# reg-board.net
KiCad netlist of a schematic drawn in EAGLE
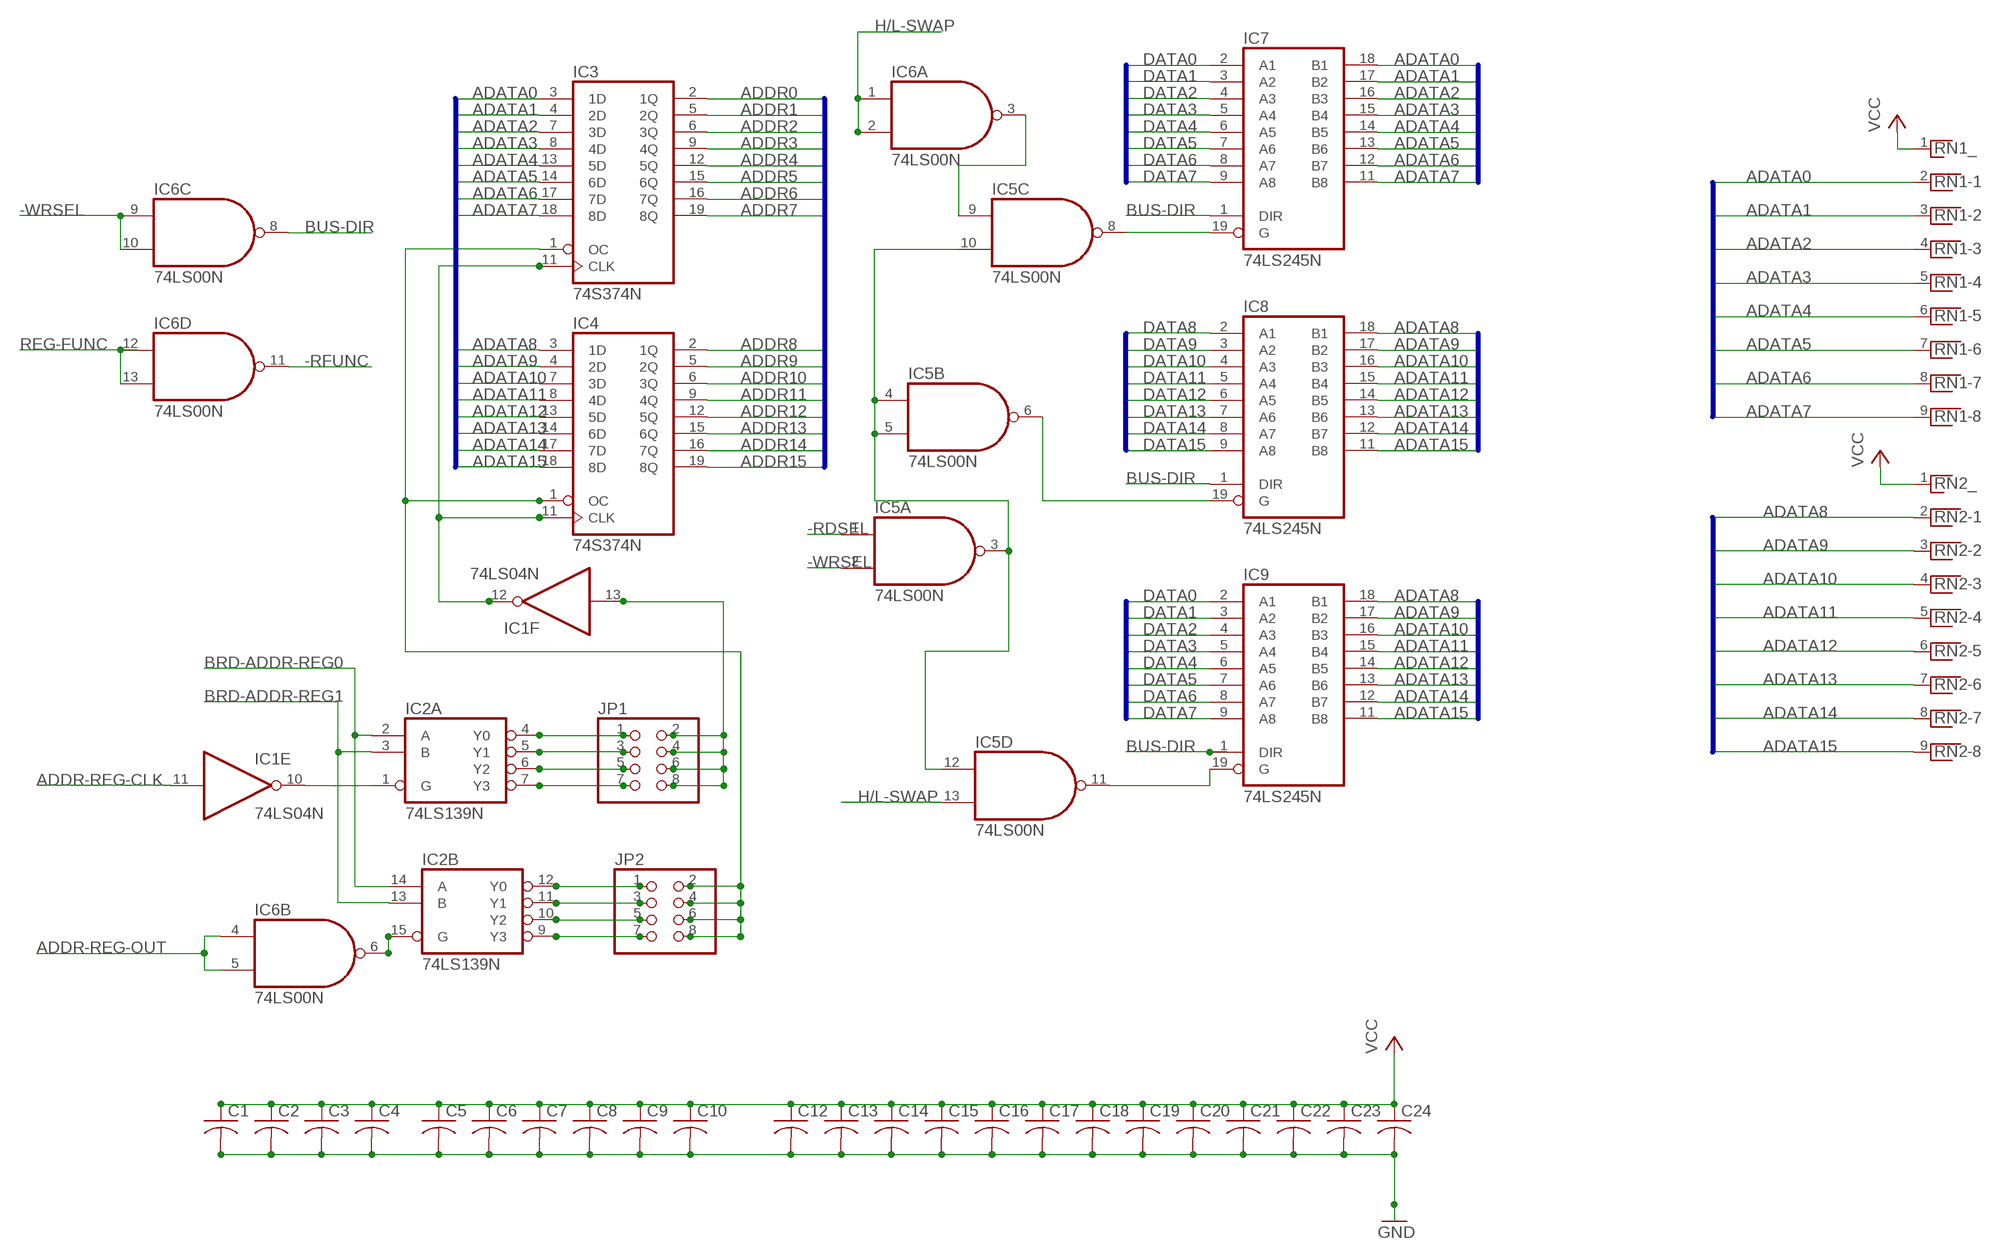
[diagram p0: schematic, sheet 1]
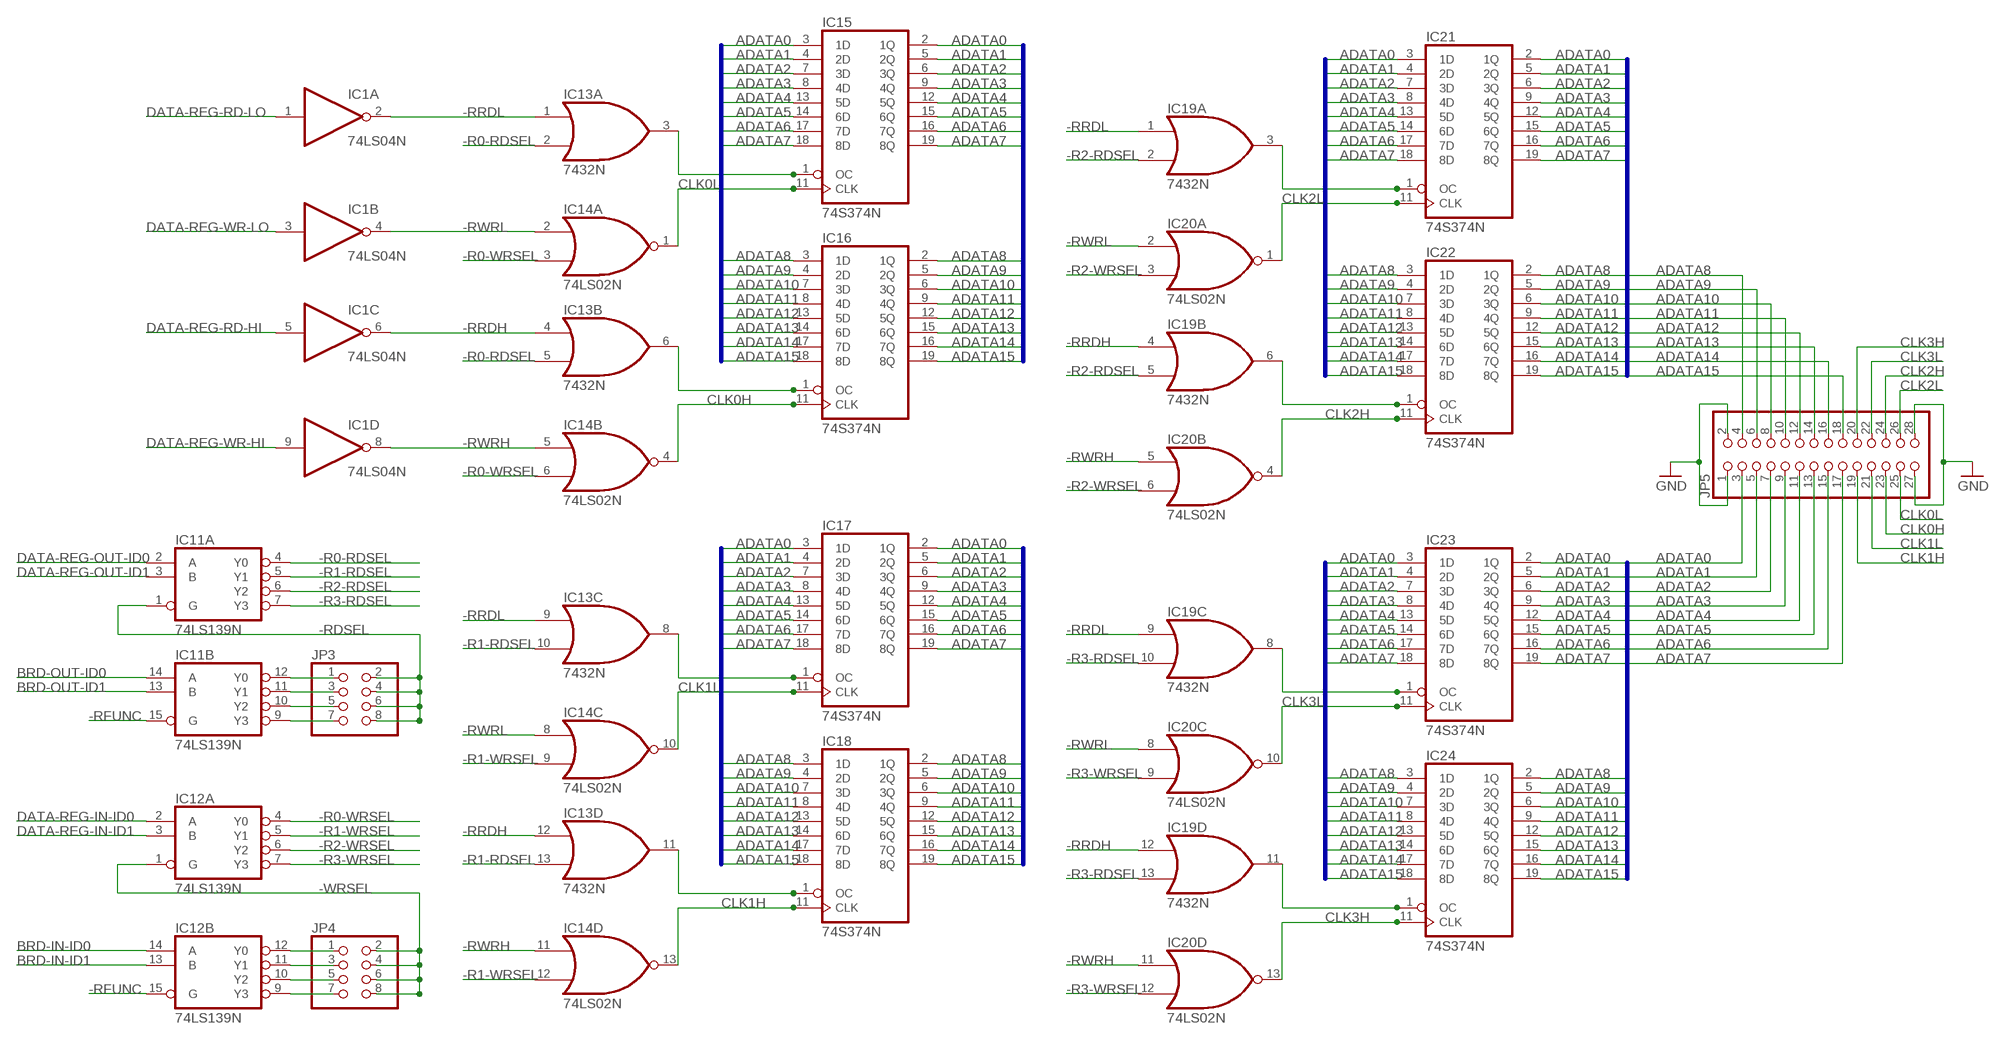
[diagram p1: schematic, sheet 2]
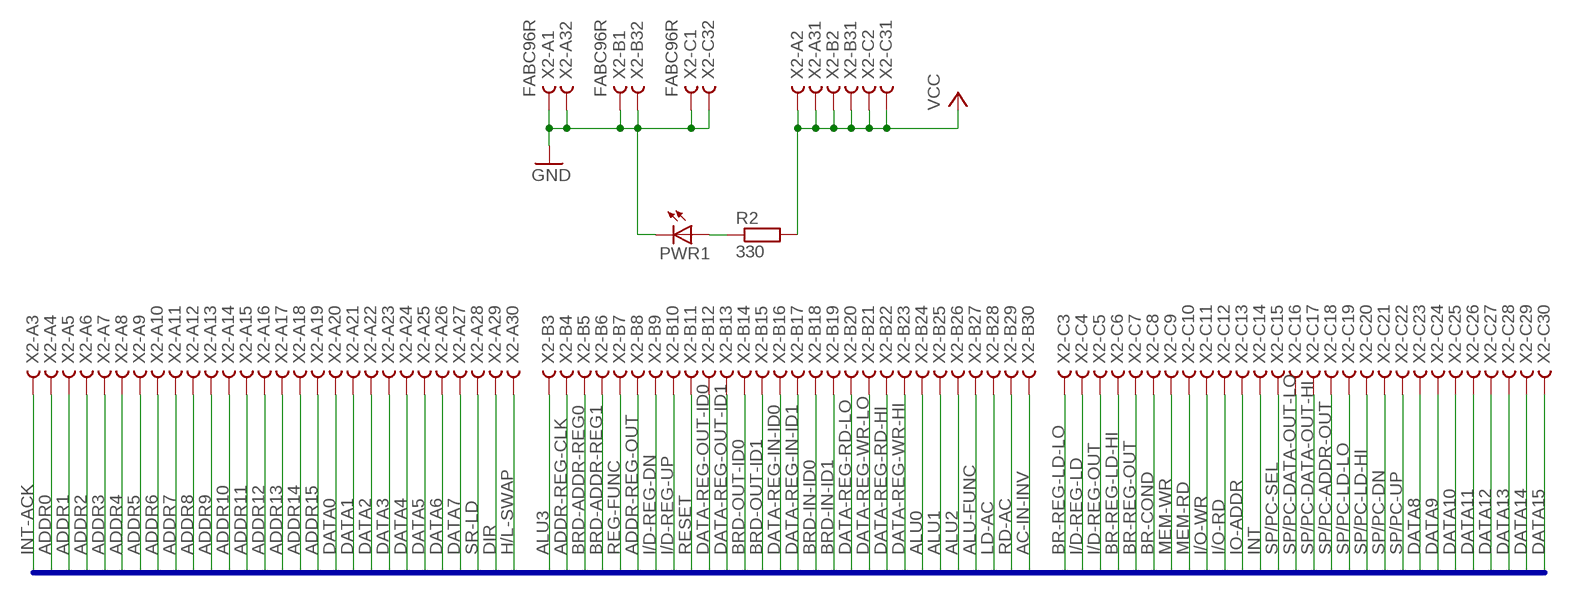
[diagram p2: schematic, sheet 3]

(export (version "E")
  (design (tool "Eeschema 10.0.6"))
  (components
    (comp (ref "IC1")
      (value "74LS04N")
      (footprint "eagle-import:DIL14")
      (libsource (lib "eagle-import") (part "7404NLS"))
    )
    (comp (ref "IC11")
      (value "74LS139N")
      (footprint "eagle-import:DIL16")
      (libsource (lib "eagle-import") (part "74139NLS"))
    )
    (comp (ref "IC12")
      (value "74LS139N")
      (footprint "eagle-import:DIL16")
      (libsource (lib "eagle-import") (part "74139NLS"))
    )
    (comp (ref "IC13")
      (value "7432N")
      (footprint "eagle-import:DIL14")
      (libsource (lib "eagle-import") (part "7432N"))
    )
    (comp (ref "IC14")
      (value "74LS02N")
      (footprint "eagle-import:DIL14")
      (libsource (lib "eagle-import") (part "7402NLS"))
    )
    (comp (ref "IC15")
      (value "74S374N")
      (footprint "eagle-import:DIL20")
      (libsource (lib "eagle-import") (part "74374NS"))
    )
    (comp (ref "IC16")
      (value "74S374N")
      (footprint "eagle-import:DIL20")
      (libsource (lib "eagle-import") (part "74374NS"))
    )
    (comp (ref "IC17")
      (value "74S374N")
      (footprint "eagle-import:DIL20")
      (libsource (lib "eagle-import") (part "74374NS"))
    )
    (comp (ref "IC18")
      (value "74S374N")
      (footprint "eagle-import:DIL20")
      (libsource (lib "eagle-import") (part "74374NS"))
    )
    (comp (ref "IC19")
      (value "7432N")
      (footprint "eagle-import:DIL14")
      (libsource (lib "eagle-import") (part "7432N"))
    )
    (comp (ref "IC20")
      (value "74LS02N")
      (footprint "eagle-import:DIL14")
      (libsource (lib "eagle-import") (part "7402NLS"))
    )
    (comp (ref "IC21")
      (value "74S374N")
      (footprint "eagle-import:DIL20")
      (libsource (lib "eagle-import") (part "74374NS"))
    )
    (comp (ref "IC22")
      (value "74S374N")
      (footprint "eagle-import:DIL20")
      (libsource (lib "eagle-import") (part "74374NS"))
    )
    (comp (ref "IC23")
      (value "74S374N")
      (footprint "eagle-import:DIL20")
      (libsource (lib "eagle-import") (part "74374NS"))
    )
    (comp (ref "IC24")
      (value "74S374N")
      (footprint "eagle-import:DIL20")
      (libsource (lib "eagle-import") (part "74374NS"))
    )
    (comp (ref "JP3")
      (value "PINHD-2X4")
      (footprint "eagle-import:2X04")
      (libsource (lib "eagle-import") (part "PINHD-2X4"))
    )
    (comp (ref "JP4")
      (value "PINHD-2X4")
      (footprint "eagle-import:2X04")
      (libsource (lib "eagle-import") (part "PINHD-2X4"))
    )
    (comp (ref "JP5")
      (value "PINHD-2X14")
      (footprint "eagle-import:2X14")
      (libsource (lib "eagle-import") (part "PINHD-2X14"))
    )
    (comp (ref "PWR1")
      (value "LED5MM")
      (footprint "eagle-import:LED5MM")
      (libsource (lib "eagle-import") (part "LED5MM"))
    )
    (comp (ref "R2")
      (value "330")
      (footprint "eagle-import:0207_10")
      (libsource (lib "eagle-import") (part "R0207/10"))
    )
    (comp (ref "X2")
      (value "FABC96R")
      (footprint "eagle-import:FABC96R")
      (libsource (lib "eagle-import") (part "FABC96R"))
    )
    (comp (ref "C1")
      (value "C-US025-040X050")
      (footprint "eagle-import:C025-040X050")
      (libsource (lib "eagle-import") (part "C-US025-040X050"))
    )
    (comp (ref "C2")
      (value "C-US025-040X050")
      (footprint "eagle-import:C025-040X050")
      (libsource (lib "eagle-import") (part "C-US025-040X050"))
    )
    (comp (ref "C3")
      (value "C-US025-040X050")
      (footprint "eagle-import:C025-040X050")
      (libsource (lib "eagle-import") (part "C-US025-040X050"))
    )
    (comp (ref "C4")
      (value "C-US025-040X050")
      (footprint "eagle-import:C025-040X050")
      (libsource (lib "eagle-import") (part "C-US025-040X050"))
    )
    (comp (ref "C5")
      (value "C-US025-040X050")
      (footprint "eagle-import:C025-040X050")
      (libsource (lib "eagle-import") (part "C-US025-040X050"))
    )
    (comp (ref "C6")
      (value "C-US025-040X050")
      (footprint "eagle-import:C025-040X050")
      (libsource (lib "eagle-import") (part "C-US025-040X050"))
    )
    (comp (ref "C7")
      (value "C-US025-040X050")
      (footprint "eagle-import:C025-040X050")
      (libsource (lib "eagle-import") (part "C-US025-040X050"))
    )
    (comp (ref "C8")
      (value "C-US025-040X050")
      (footprint "eagle-import:C025-040X050")
      (libsource (lib "eagle-import") (part "C-US025-040X050"))
    )
    (comp (ref "C9")
      (value "C-US025-040X050")
      (footprint "eagle-import:C025-040X050")
      (libsource (lib "eagle-import") (part "C-US025-040X050"))
    )
    (comp (ref "C10")
      (value "C-US025-040X050")
      (footprint "eagle-import:C025-040X050")
      (libsource (lib "eagle-import") (part "C-US025-040X050"))
    )
    (comp (ref "C12")
      (value "C-US025-040X050")
      (footprint "eagle-import:C025-040X050")
      (libsource (lib "eagle-import") (part "C-US025-040X050"))
    )
    (comp (ref "C13")
      (value "C-US025-040X050")
      (footprint "eagle-import:C025-040X050")
      (libsource (lib "eagle-import") (part "C-US025-040X050"))
    )
    (comp (ref "C14")
      (value "C-US025-040X050")
      (footprint "eagle-import:C025-040X050")
      (libsource (lib "eagle-import") (part "C-US025-040X050"))
    )
    (comp (ref "C15")
      (value "C-US025-040X050")
      (footprint "eagle-import:C025-040X050")
      (libsource (lib "eagle-import") (part "C-US025-040X050"))
    )
    (comp (ref "C16")
      (value "C-US025-040X050")
      (footprint "eagle-import:C025-040X050")
      (libsource (lib "eagle-import") (part "C-US025-040X050"))
    )
    (comp (ref "C17")
      (value "C-US025-040X050")
      (footprint "eagle-import:C025-040X050")
      (libsource (lib "eagle-import") (part "C-US025-040X050"))
    )
    (comp (ref "C18")
      (value "C-US025-040X050")
      (footprint "eagle-import:C025-040X050")
      (libsource (lib "eagle-import") (part "C-US025-040X050"))
    )
    (comp (ref "C19")
      (value "C-US025-040X050")
      (footprint "eagle-import:C025-040X050")
      (libsource (lib "eagle-import") (part "C-US025-040X050"))
    )
    (comp (ref "C20")
      (value "C-US025-040X050")
      (footprint "eagle-import:C025-040X050")
      (libsource (lib "eagle-import") (part "C-US025-040X050"))
    )
    (comp (ref "C21")
      (value "C-US025-040X050")
      (footprint "eagle-import:C025-040X050")
      (libsource (lib "eagle-import") (part "C-US025-040X050"))
    )
    (comp (ref "C22")
      (value "C-US025-040X050")
      (footprint "eagle-import:C025-040X050")
      (libsource (lib "eagle-import") (part "C-US025-040X050"))
    )
    (comp (ref "C23")
      (value "C-US025-040X050")
      (footprint "eagle-import:C025-040X050")
      (libsource (lib "eagle-import") (part "C-US025-040X050"))
    )
    (comp (ref "C24")
      (value "C-US025-040X050")
      (footprint "eagle-import:C025-040X050")
      (libsource (lib "eagle-import") (part "C-US025-040X050"))
    )
    (comp (ref "IC2")
      (value "74LS139N")
      (footprint "eagle-import:DIL16")
      (libsource (lib "eagle-import") (part "74139NLS"))
    )
    (comp (ref "IC3")
      (value "74S374N")
      (footprint "eagle-import:DIL20")
      (libsource (lib "eagle-import") (part "74374NS"))
    )
    (comp (ref "IC4")
      (value "74S374N")
      (footprint "eagle-import:DIL20")
      (libsource (lib "eagle-import") (part "74374NS"))
    )
    (comp (ref "IC5")
      (value "74LS00N")
      (footprint "eagle-import:DIL14")
      (libsource (lib "eagle-import") (part "7400NLS"))
    )
    (comp (ref "IC6")
      (value "74LS00N")
      (footprint "eagle-import:DIL14")
      (libsource (lib "eagle-import") (part "7400NLS"))
    )
    (comp (ref "IC7")
      (value "74LS245N")
      (footprint "eagle-import:DIL20")
      (libsource (lib "eagle-import") (part "74245NLS"))
    )
    (comp (ref "IC8")
      (value "74LS245N")
      (footprint "eagle-import:DIL20")
      (libsource (lib "eagle-import") (part "74245NLS"))
    )
    (comp (ref "IC9")
      (value "74LS245N")
      (footprint "eagle-import:DIL20")
      (libsource (lib "eagle-import") (part "74245NLS"))
    )
    (comp (ref "JP1")
      (value "PINHD-2X4")
      (footprint "eagle-import:2X04")
      (libsource (lib "eagle-import") (part "PINHD-2X4"))
    )
    (comp (ref "JP2")
      (value "PINHD-2X4")
      (footprint "eagle-import:2X04")
      (libsource (lib "eagle-import") (part "PINHD-2X4"))
    )
    (comp (ref "RN1")
      (value "RNX8")
      (footprint "eagle-import:RN-9")
      (libsource (lib "eagle-import") (part "RNX8"))
    )
    (comp (ref "RN2")
      (value "RNX8")
      (footprint "eagle-import:RN-9")
      (libsource (lib "eagle-import") (part "RNX8"))
    )
  )
  (nets
    (net (code "1") (name "-R0-RDSEL") (class "Default")
      (node (ref "IC11") (pin "4") (pinfunction "Y0_4") (pintype "output"))
      (node (ref "IC13") (pin "2") (pinfunction "I1_2") (pintype "input"))
      (node (ref "IC13") (pin "5") (pinfunction "I1_5") (pintype "input"))
    )
    (net (code "2") (name "-R0-WRSEL") (class "Default")
      (node (ref "IC12") (pin "4") (pinfunction "Y0_4") (pintype "output"))
      (node (ref "IC14") (pin "3") (pinfunction "I1_3") (pintype "input"))
      (node (ref "IC14") (pin "6") (pinfunction "I1_6") (pintype "input"))
    )
    (net (code "3") (name "-R1-RDSEL") (class "Default")
      (node (ref "IC11") (pin "5") (pinfunction "Y1_5") (pintype "output"))
      (node (ref "IC13") (pin "10") (pinfunction "I1_10") (pintype "input"))
      (node (ref "IC13") (pin "13") (pinfunction "I1_13") (pintype "input"))
    )
    (net (code "4") (name "-R1-WRSEL") (class "Default")
      (node (ref "IC12") (pin "5") (pinfunction "Y1_5") (pintype "output"))
      (node (ref "IC14") (pin "12") (pinfunction "I1_12") (pintype "input"))
      (node (ref "IC14") (pin "9") (pinfunction "I1_9") (pintype "input"))
    )
    (net (code "5") (name "-R2-RDSEL") (class "Default")
      (node (ref "IC11") (pin "6") (pinfunction "Y2_6") (pintype "output"))
      (node (ref "IC19") (pin "2") (pinfunction "I1_2") (pintype "input"))
      (node (ref "IC19") (pin "5") (pinfunction "I1_5") (pintype "input"))
    )
    (net (code "6") (name "-R2-WRSEL") (class "Default")
      (node (ref "IC12") (pin "6") (pinfunction "Y2_6") (pintype "output"))
      (node (ref "IC20") (pin "3") (pinfunction "I1_3") (pintype "input"))
      (node (ref "IC20") (pin "6") (pinfunction "I1_6") (pintype "input"))
    )
    (net (code "7") (name "-R3-RDSEL") (class "Default")
      (node (ref "IC11") (pin "7") (pinfunction "Y3_7") (pintype "output"))
      (node (ref "IC19") (pin "10") (pinfunction "I1_10") (pintype "input"))
      (node (ref "IC19") (pin "13") (pinfunction "I1_13") (pintype "input"))
    )
    (net (code "8") (name "-R3-WRSEL") (class "Default")
      (node (ref "IC12") (pin "7") (pinfunction "Y3_7") (pintype "output"))
      (node (ref "IC20") (pin "12") (pinfunction "I1_12") (pintype "input"))
      (node (ref "IC20") (pin "9") (pinfunction "I1_9") (pintype "input"))
    )
    (net (code "9") (name "-RDSEL") (class "Default")
      (node (ref "IC11") (pin "1") (pinfunction "G_1") (pintype "input"))
      (node (ref "IC5") (pin "1") (pinfunction "I0_1") (pintype "input"))
      (node (ref "JP3") (pin "2") (pinfunction "2_2") (pintype "passive"))
      (node (ref "JP3") (pin "4") (pinfunction "4_4") (pintype "passive"))
      (node (ref "JP3") (pin "6") (pinfunction "6_6") (pintype "passive"))
      (node (ref "JP3") (pin "8") (pinfunction "8_8") (pintype "passive"))
    )
    (net (code "10") (name "-RFUNC") (class "Default")
      (node (ref "IC11") (pin "15") (pinfunction "G_15") (pintype "input"))
      (node (ref "IC12") (pin "15") (pinfunction "G_15") (pintype "input"))
      (node (ref "IC6") (pin "11") (pinfunction "O_11") (pintype "output"))
    )
    (net (code "11") (name "-RRDH") (class "Default")
      (node (ref "IC1") (pin "6") (pinfunction "O_6") (pintype "output"))
      (node (ref "IC13") (pin "12") (pinfunction "I0_12") (pintype "input"))
      (node (ref "IC13") (pin "4") (pinfunction "I0_4") (pintype "input"))
      (node (ref "IC19") (pin "12") (pinfunction "I0_12") (pintype "input"))
      (node (ref "IC19") (pin "4") (pinfunction "I0_4") (pintype "input"))
    )
    (net (code "12") (name "-RRDL") (class "Default")
      (node (ref "IC1") (pin "2") (pinfunction "O_2") (pintype "output"))
      (node (ref "IC13") (pin "1") (pinfunction "I0_1") (pintype "input"))
      (node (ref "IC13") (pin "9") (pinfunction "I0_9") (pintype "input"))
      (node (ref "IC19") (pin "1") (pinfunction "I0_1") (pintype "input"))
      (node (ref "IC19") (pin "9") (pinfunction "I0_9") (pintype "input"))
    )
    (net (code "13") (name "-RWRH") (class "Default")
      (node (ref "IC1") (pin "8") (pinfunction "O_8") (pintype "output"))
      (node (ref "IC14") (pin "11") (pinfunction "I0_11") (pintype "input"))
      (node (ref "IC14") (pin "5") (pinfunction "I0_5") (pintype "input"))
      (node (ref "IC20") (pin "11") (pinfunction "I0_11") (pintype "input"))
      (node (ref "IC20") (pin "5") (pinfunction "I0_5") (pintype "input"))
    )
    (net (code "14") (name "-RWRL") (class "Default")
      (node (ref "IC1") (pin "4") (pinfunction "O_4") (pintype "output"))
      (node (ref "IC14") (pin "2") (pinfunction "I0_2") (pintype "input"))
      (node (ref "IC14") (pin "8") (pinfunction "I0_8") (pintype "input"))
      (node (ref "IC20") (pin "2") (pinfunction "I0_2") (pintype "input"))
      (node (ref "IC20") (pin "8") (pinfunction "I0_8") (pintype "input"))
    )
    (net (code "15") (name "-WRSEL") (class "Default")
      (node (ref "IC12") (pin "1") (pinfunction "G_1") (pintype "input"))
      (node (ref "IC5") (pin "2") (pinfunction "I1_2") (pintype "input"))
      (node (ref "IC6") (pin "10") (pinfunction "I1_10") (pintype "input"))
      (node (ref "IC6") (pin "9") (pinfunction "I0_9") (pintype "input"))
      (node (ref "JP4") (pin "2") (pinfunction "2_2") (pintype "passive"))
      (node (ref "JP4") (pin "4") (pinfunction "4_4") (pintype "passive"))
      (node (ref "JP4") (pin "6") (pinfunction "6_6") (pintype "passive"))
      (node (ref "JP4") (pin "8") (pinfunction "8_8") (pintype "passive"))
    )
    (net (code "16") (name "AC-IN-INV") (class "Default")
      (node (ref "X2") (pin "B30") (pinfunction "B_B30") (pintype "passive"))
    )
    (net (code "17") (name "ADATA0") (class "Default")
      (node (ref "IC15") (pin "2") (pinfunction "1Q_2") (pintype "tri_state"))
      (node (ref "IC15") (pin "3") (pinfunction "1D_3") (pintype "input"))
      (node (ref "IC17") (pin "2") (pinfunction "1Q_2") (pintype "tri_state"))
      (node (ref "IC17") (pin "3") (pinfunction "1D_3") (pintype "input"))
      (node (ref "IC21") (pin "2") (pinfunction "1Q_2") (pintype "tri_state"))
      (node (ref "IC21") (pin "3") (pinfunction "1D_3") (pintype "input"))
      (node (ref "IC23") (pin "2") (pinfunction "1Q_2") (pintype "tri_state"))
      (node (ref "IC23") (pin "3") (pinfunction "1D_3") (pintype "input"))
      (node (ref "IC3") (pin "3") (pinfunction "1D_3") (pintype "input"))
      (node (ref "IC7") (pin "18") (pinfunction "B1_18") (pintype "bidirectional"))
      (node (ref "JP5") (pin "3") (pinfunction "3_3") (pintype "passive"))
      (node (ref "RN1") (pin "2") (pinfunction "1_2") (pintype "passive"))
    )
    (net (code "18") (name "ADATA1") (class "Default")
      (node (ref "IC15") (pin "4") (pinfunction "2D_4") (pintype "input"))
      (node (ref "IC15") (pin "5") (pinfunction "2Q_5") (pintype "tri_state"))
      (node (ref "IC17") (pin "4") (pinfunction "2D_4") (pintype "input"))
      (node (ref "IC17") (pin "5") (pinfunction "2Q_5") (pintype "tri_state"))
      (node (ref "IC21") (pin "4") (pinfunction "2D_4") (pintype "input"))
      (node (ref "IC21") (pin "5") (pinfunction "2Q_5") (pintype "tri_state"))
      (node (ref "IC23") (pin "4") (pinfunction "2D_4") (pintype "input"))
      (node (ref "IC23") (pin "5") (pinfunction "2Q_5") (pintype "tri_state"))
      (node (ref "IC3") (pin "4") (pinfunction "2D_4") (pintype "input"))
      (node (ref "IC7") (pin "17") (pinfunction "B2_17") (pintype "bidirectional"))
      (node (ref "JP5") (pin "5") (pinfunction "5_5") (pintype "passive"))
      (node (ref "RN1") (pin "3") (pinfunction "1_3") (pintype "passive"))
    )
    (net (code "19") (name "ADATA2") (class "Default")
      (node (ref "IC15") (pin "6") (pinfunction "3Q_6") (pintype "tri_state"))
      (node (ref "IC15") (pin "7") (pinfunction "3D_7") (pintype "input"))
      (node (ref "IC17") (pin "6") (pinfunction "3Q_6") (pintype "tri_state"))
      (node (ref "IC17") (pin "7") (pinfunction "3D_7") (pintype "input"))
      (node (ref "IC21") (pin "6") (pinfunction "3Q_6") (pintype "tri_state"))
      (node (ref "IC21") (pin "7") (pinfunction "3D_7") (pintype "input"))
      (node (ref "IC23") (pin "6") (pinfunction "3Q_6") (pintype "tri_state"))
      (node (ref "IC23") (pin "7") (pinfunction "3D_7") (pintype "input"))
      (node (ref "IC3") (pin "7") (pinfunction "3D_7") (pintype "input"))
      (node (ref "IC7") (pin "16") (pinfunction "B3_16") (pintype "bidirectional"))
      (node (ref "JP5") (pin "7") (pinfunction "7_7") (pintype "passive"))
      (node (ref "RN1") (pin "4") (pinfunction "1_4") (pintype "passive"))
    )
    (net (code "20") (name "ADATA3") (class "Default")
      (node (ref "IC15") (pin "8") (pinfunction "4D_8") (pintype "input"))
      (node (ref "IC15") (pin "9") (pinfunction "4Q_9") (pintype "tri_state"))
      (node (ref "IC17") (pin "8") (pinfunction "4D_8") (pintype "input"))
      (node (ref "IC17") (pin "9") (pinfunction "4Q_9") (pintype "tri_state"))
      (node (ref "IC21") (pin "8") (pinfunction "4D_8") (pintype "input"))
      (node (ref "IC21") (pin "9") (pinfunction "4Q_9") (pintype "tri_state"))
      (node (ref "IC23") (pin "8") (pinfunction "4D_8") (pintype "input"))
      (node (ref "IC23") (pin "9") (pinfunction "4Q_9") (pintype "tri_state"))
      (node (ref "IC3") (pin "8") (pinfunction "4D_8") (pintype "input"))
      (node (ref "IC7") (pin "15") (pinfunction "B4_15") (pintype "bidirectional"))
      (node (ref "JP5") (pin "9") (pinfunction "9_9") (pintype "passive"))
      (node (ref "RN1") (pin "5") (pinfunction "1_5") (pintype "passive"))
    )
    (net (code "21") (name "ADATA4") (class "Default")
      (node (ref "IC15") (pin "12") (pinfunction "5Q_12") (pintype "tri_state"))
      (node (ref "IC15") (pin "13") (pinfunction "5D_13") (pintype "input"))
      (node (ref "IC17") (pin "12") (pinfunction "5Q_12") (pintype "tri_state"))
      (node (ref "IC17") (pin "13") (pinfunction "5D_13") (pintype "input"))
      (node (ref "IC21") (pin "12") (pinfunction "5Q_12") (pintype "tri_state"))
      (node (ref "IC21") (pin "13") (pinfunction "5D_13") (pintype "input"))
      (node (ref "IC23") (pin "12") (pinfunction "5Q_12") (pintype "tri_state"))
      (node (ref "IC23") (pin "13") (pinfunction "5D_13") (pintype "input"))
      (node (ref "IC3") (pin "13") (pinfunction "5D_13") (pintype "input"))
      (node (ref "IC7") (pin "14") (pinfunction "B5_14") (pintype "bidirectional"))
      (node (ref "JP5") (pin "11") (pinfunction "11_11") (pintype "passive"))
      (node (ref "RN1") (pin "6") (pinfunction "1_6") (pintype "passive"))
    )
    (net (code "22") (name "ADATA5") (class "Default")
      (node (ref "IC15") (pin "14") (pinfunction "6D_14") (pintype "input"))
      (node (ref "IC15") (pin "15") (pinfunction "6Q_15") (pintype "tri_state"))
      (node (ref "IC17") (pin "14") (pinfunction "6D_14") (pintype "input"))
      (node (ref "IC17") (pin "15") (pinfunction "6Q_15") (pintype "tri_state"))
      (node (ref "IC21") (pin "14") (pinfunction "6D_14") (pintype "input"))
      (node (ref "IC21") (pin "15") (pinfunction "6Q_15") (pintype "tri_state"))
      (node (ref "IC23") (pin "14") (pinfunction "6D_14") (pintype "input"))
      (node (ref "IC23") (pin "15") (pinfunction "6Q_15") (pintype "tri_state"))
      (node (ref "IC3") (pin "14") (pinfunction "6D_14") (pintype "input"))
      (node (ref "IC7") (pin "13") (pinfunction "B6_13") (pintype "bidirectional"))
      (node (ref "JP5") (pin "13") (pinfunction "13_13") (pintype "passive"))
      (node (ref "RN1") (pin "7") (pinfunction "1_7") (pintype "passive"))
    )
    (net (code "23") (name "ADATA6") (class "Default")
      (node (ref "IC15") (pin "16") (pinfunction "7Q_16") (pintype "tri_state"))
      (node (ref "IC15") (pin "17") (pinfunction "7D_17") (pintype "input"))
      (node (ref "IC17") (pin "16") (pinfunction "7Q_16") (pintype "tri_state"))
      (node (ref "IC17") (pin "17") (pinfunction "7D_17") (pintype "input"))
      (node (ref "IC21") (pin "16") (pinfunction "7Q_16") (pintype "tri_state"))
      (node (ref "IC21") (pin "17") (pinfunction "7D_17") (pintype "input"))
      (node (ref "IC23") (pin "16") (pinfunction "7Q_16") (pintype "tri_state"))
      (node (ref "IC23") (pin "17") (pinfunction "7D_17") (pintype "input"))
      (node (ref "IC3") (pin "17") (pinfunction "7D_17") (pintype "input"))
      (node (ref "IC7") (pin "12") (pinfunction "B7_12") (pintype "bidirectional"))
      (node (ref "JP5") (pin "15") (pinfunction "15_15") (pintype "passive"))
      (node (ref "RN1") (pin "8") (pinfunction "1_8") (pintype "passive"))
    )
    (net (code "24") (name "ADATA7") (class "Default")
      (node (ref "IC15") (pin "18") (pinfunction "8D_18") (pintype "input"))
      (node (ref "IC15") (pin "19") (pinfunction "8Q_19") (pintype "tri_state"))
      (node (ref "IC17") (pin "18") (pinfunction "8D_18") (pintype "input"))
      (node (ref "IC17") (pin "19") (pinfunction "8Q_19") (pintype "tri_state"))
      (node (ref "IC21") (pin "18") (pinfunction "8D_18") (pintype "input"))
      (node (ref "IC21") (pin "19") (pinfunction "8Q_19") (pintype "tri_state"))
      (node (ref "IC23") (pin "18") (pinfunction "8D_18") (pintype "input"))
      (node (ref "IC23") (pin "19") (pinfunction "8Q_19") (pintype "tri_state"))
      (node (ref "IC3") (pin "18") (pinfunction "8D_18") (pintype "input"))
      (node (ref "IC7") (pin "11") (pinfunction "B8_11") (pintype "bidirectional"))
      (node (ref "JP5") (pin "17") (pinfunction "17_17") (pintype "passive"))
      (node (ref "RN1") (pin "9") (pinfunction "1_9") (pintype "passive"))
    )
    (net (code "25") (name "ADATA8") (class "Default")
      (node (ref "IC16") (pin "2") (pinfunction "1Q_2") (pintype "tri_state"))
      (node (ref "IC16") (pin "3") (pinfunction "1D_3") (pintype "input"))
      (node (ref "IC18") (pin "2") (pinfunction "1Q_2") (pintype "tri_state"))
      (node (ref "IC18") (pin "3") (pinfunction "1D_3") (pintype "input"))
      (node (ref "IC22") (pin "2") (pinfunction "1Q_2") (pintype "tri_state"))
      (node (ref "IC22") (pin "3") (pinfunction "1D_3") (pintype "input"))
      (node (ref "IC24") (pin "2") (pinfunction "1Q_2") (pintype "tri_state"))
      (node (ref "IC24") (pin "3") (pinfunction "1D_3") (pintype "input"))
      (node (ref "IC4") (pin "3") (pinfunction "1D_3") (pintype "input"))
      (node (ref "IC8") (pin "18") (pinfunction "B1_18") (pintype "bidirectional"))
      (node (ref "IC9") (pin "18") (pinfunction "B1_18") (pintype "bidirectional"))
      (node (ref "JP5") (pin "4") (pinfunction "4_4") (pintype "passive"))
      (node (ref "RN2") (pin "2") (pinfunction "1_2") (pintype "passive"))
    )
    (net (code "26") (name "ADATA9") (class "Default")
      (node (ref "IC16") (pin "4") (pinfunction "2D_4") (pintype "input"))
      (node (ref "IC16") (pin "5") (pinfunction "2Q_5") (pintype "tri_state"))
      (node (ref "IC18") (pin "4") (pinfunction "2D_4") (pintype "input"))
      (node (ref "IC18") (pin "5") (pinfunction "2Q_5") (pintype "tri_state"))
      (node (ref "IC22") (pin "4") (pinfunction "2D_4") (pintype "input"))
      (node (ref "IC22") (pin "5") (pinfunction "2Q_5") (pintype "tri_state"))
      (node (ref "IC24") (pin "4") (pinfunction "2D_4") (pintype "input"))
      (node (ref "IC24") (pin "5") (pinfunction "2Q_5") (pintype "tri_state"))
      (node (ref "IC4") (pin "4") (pinfunction "2D_4") (pintype "input"))
      (node (ref "IC8") (pin "17") (pinfunction "B2_17") (pintype "bidirectional"))
      (node (ref "IC9") (pin "17") (pinfunction "B2_17") (pintype "bidirectional"))
      (node (ref "JP5") (pin "6") (pinfunction "6_6") (pintype "passive"))
      (node (ref "RN2") (pin "3") (pinfunction "1_3") (pintype "passive"))
    )
    (net (code "27") (name "ADATA10") (class "Default")
      (node (ref "IC16") (pin "6") (pinfunction "3Q_6") (pintype "tri_state"))
      (node (ref "IC16") (pin "7") (pinfunction "3D_7") (pintype "input"))
      (node (ref "IC18") (pin "6") (pinfunction "3Q_6") (pintype "tri_state"))
      (node (ref "IC18") (pin "7") (pinfunction "3D_7") (pintype "input"))
      (node (ref "IC22") (pin "6") (pinfunction "3Q_6") (pintype "tri_state"))
      (node (ref "IC22") (pin "7") (pinfunction "3D_7") (pintype "input"))
      (node (ref "IC24") (pin "6") (pinfunction "3Q_6") (pintype "tri_state"))
      (node (ref "IC24") (pin "7") (pinfunction "3D_7") (pintype "input"))
      (node (ref "IC4") (pin "7") (pinfunction "3D_7") (pintype "input"))
      (node (ref "IC8") (pin "16") (pinfunction "B3_16") (pintype "bidirectional"))
      (node (ref "IC9") (pin "16") (pinfunction "B3_16") (pintype "bidirectional"))
      (node (ref "JP5") (pin "8") (pinfunction "8_8") (pintype "passive"))
      (node (ref "RN2") (pin "4") (pinfunction "1_4") (pintype "passive"))
    )
    (net (code "28") (name "ADATA11") (class "Default")
      (node (ref "IC16") (pin "8") (pinfunction "4D_8") (pintype "input"))
      (node (ref "IC16") (pin "9") (pinfunction "4Q_9") (pintype "tri_state"))
      (node (ref "IC18") (pin "8") (pinfunction "4D_8") (pintype "input"))
      (node (ref "IC18") (pin "9") (pinfunction "4Q_9") (pintype "tri_state"))
      (node (ref "IC22") (pin "8") (pinfunction "4D_8") (pintype "input"))
      (node (ref "IC22") (pin "9") (pinfunction "4Q_9") (pintype "tri_state"))
      (node (ref "IC24") (pin "8") (pinfunction "4D_8") (pintype "input"))
      (node (ref "IC24") (pin "9") (pinfunction "4Q_9") (pintype "tri_state"))
      (node (ref "IC4") (pin "8") (pinfunction "4D_8") (pintype "input"))
      (node (ref "IC8") (pin "15") (pinfunction "B4_15") (pintype "bidirectional"))
      (node (ref "IC9") (pin "15") (pinfunction "B4_15") (pintype "bidirectional"))
      (node (ref "JP5") (pin "10") (pinfunction "10_10") (pintype "passive"))
      (node (ref "RN2") (pin "5") (pinfunction "1_5") (pintype "passive"))
    )
    (net (code "29") (name "ADATA12") (class "Default")
      (node (ref "IC16") (pin "12") (pinfunction "5Q_12") (pintype "tri_state"))
      (node (ref "IC16") (pin "13") (pinfunction "5D_13") (pintype "input"))
      (node (ref "IC18") (pin "12") (pinfunction "5Q_12") (pintype "tri_state"))
      (node (ref "IC18") (pin "13") (pinfunction "5D_13") (pintype "input"))
      (node (ref "IC22") (pin "12") (pinfunction "5Q_12") (pintype "tri_state"))
      (node (ref "IC22") (pin "13") (pinfunction "5D_13") (pintype "input"))
      (node (ref "IC24") (pin "12") (pinfunction "5Q_12") (pintype "tri_state"))
      (node (ref "IC24") (pin "13") (pinfunction "5D_13") (pintype "input"))
      (node (ref "IC4") (pin "13") (pinfunction "5D_13") (pintype "input"))
      (node (ref "IC8") (pin "14") (pinfunction "B5_14") (pintype "bidirectional"))
      (node (ref "IC9") (pin "14") (pinfunction "B5_14") (pintype "bidirectional"))
      (node (ref "JP5") (pin "12") (pinfunction "12_12") (pintype "passive"))
      (node (ref "RN2") (pin "6") (pinfunction "1_6") (pintype "passive"))
    )
    (net (code "30") (name "ADATA13") (class "Default")
      (node (ref "IC16") (pin "14") (pinfunction "6D_14") (pintype "input"))
      (node (ref "IC16") (pin "15") (pinfunction "6Q_15") (pintype "tri_state"))
      (node (ref "IC18") (pin "14") (pinfunction "6D_14") (pintype "input"))
      (node (ref "IC18") (pin "15") (pinfunction "6Q_15") (pintype "tri_state"))
      (node (ref "IC22") (pin "14") (pinfunction "6D_14") (pintype "input"))
      (node (ref "IC22") (pin "15") (pinfunction "6Q_15") (pintype "tri_state"))
      (node (ref "IC24") (pin "14") (pinfunction "6D_14") (pintype "input"))
      (node (ref "IC24") (pin "15") (pinfunction "6Q_15") (pintype "tri_state"))
      (node (ref "IC4") (pin "14") (pinfunction "6D_14") (pintype "input"))
      (node (ref "IC8") (pin "13") (pinfunction "B6_13") (pintype "bidirectional"))
      (node (ref "IC9") (pin "13") (pinfunction "B6_13") (pintype "bidirectional"))
      (node (ref "JP5") (pin "14") (pinfunction "14_14") (pintype "passive"))
      (node (ref "RN2") (pin "7") (pinfunction "1_7") (pintype "passive"))
    )
    (net (code "31") (name "ADATA14") (class "Default")
      (node (ref "IC16") (pin "16") (pinfunction "7Q_16") (pintype "tri_state"))
      (node (ref "IC16") (pin "17") (pinfunction "7D_17") (pintype "input"))
      (node (ref "IC18") (pin "16") (pinfunction "7Q_16") (pintype "tri_state"))
      (node (ref "IC18") (pin "17") (pinfunction "7D_17") (pintype "input"))
      (node (ref "IC22") (pin "16") (pinfunction "7Q_16") (pintype "tri_state"))
      (node (ref "IC22") (pin "17") (pinfunction "7D_17") (pintype "input"))
      (node (ref "IC24") (pin "16") (pinfunction "7Q_16") (pintype "tri_state"))
      (node (ref "IC24") (pin "17") (pinfunction "7D_17") (pintype "input"))
      (node (ref "IC4") (pin "17") (pinfunction "7D_17") (pintype "input"))
      (node (ref "IC8") (pin "12") (pinfunction "B7_12") (pintype "bidirectional"))
      (node (ref "IC9") (pin "12") (pinfunction "B7_12") (pintype "bidirectional"))
      (node (ref "JP5") (pin "16") (pinfunction "16_16") (pintype "passive"))
      (node (ref "RN2") (pin "8") (pinfunction "1_8") (pintype "passive"))
    )
    (net (code "32") (name "ADATA15") (class "Default")
      (node (ref "IC16") (pin "18") (pinfunction "8D_18") (pintype "input"))
      (node (ref "IC16") (pin "19") (pinfunction "8Q_19") (pintype "tri_state"))
      (node (ref "IC18") (pin "18") (pinfunction "8D_18") (pintype "input"))
      (node (ref "IC18") (pin "19") (pinfunction "8Q_19") (pintype "tri_state"))
      (node (ref "IC22") (pin "18") (pinfunction "8D_18") (pintype "input"))
      (node (ref "IC22") (pin "19") (pinfunction "8Q_19") (pintype "tri_state"))
      (node (ref "IC24") (pin "18") (pinfunction "8D_18") (pintype "input"))
      (node (ref "IC24") (pin "19") (pinfunction "8Q_19") (pintype "tri_state"))
      (node (ref "IC4") (pin "18") (pinfunction "8D_18") (pintype "input"))
      (node (ref "IC8") (pin "11") (pinfunction "B8_11") (pintype "bidirectional"))
      (node (ref "IC9") (pin "11") (pinfunction "B8_11") (pintype "bidirectional"))
      (node (ref "JP5") (pin "18") (pinfunction "18_18") (pintype "passive"))
      (node (ref "RN2") (pin "9") (pinfunction "1_9") (pintype "passive"))
    )
    (net (code "33") (name "ADDR-REG-CLK") (class "Default")
      (node (ref "IC1") (pin "11") (pinfunction "I_11") (pintype "input"))
      (node (ref "X2") (pin "B4") (pinfunction "B_B4") (pintype "passive"))
    )
    (net (code "34") (name "ADDR-REG-OUT") (class "Default")
      (node (ref "IC6") (pin "4") (pinfunction "I0_4") (pintype "input"))
      (node (ref "IC6") (pin "5") (pinfunction "I1_5") (pintype "input"))
      (node (ref "X2") (pin "B8") (pinfunction "B_B8") (pintype "passive"))
    )
    (net (code "35") (name "ADDR0") (class "Default")
      (node (ref "IC3") (pin "2") (pinfunction "1Q_2") (pintype "tri_state"))
      (node (ref "X2") (pin "A4") (pinfunction "B_A4") (pintype "passive"))
    )
    (net (code "36") (name "ADDR1") (class "Default")
      (node (ref "IC3") (pin "5") (pinfunction "2Q_5") (pintype "tri_state"))
      (node (ref "X2") (pin "A5") (pinfunction "B_A5") (pintype "passive"))
    )
    (net (code "37") (name "ADDR2") (class "Default")
      (node (ref "IC3") (pin "6") (pinfunction "3Q_6") (pintype "tri_state"))
      (node (ref "X2") (pin "A6") (pinfunction "B_A6") (pintype "passive"))
    )
    (net (code "38") (name "ADDR3") (class "Default")
      (node (ref "IC3") (pin "9") (pinfunction "4Q_9") (pintype "tri_state"))
      (node (ref "X2") (pin "A7") (pinfunction "B_A7") (pintype "passive"))
    )
    (net (code "39") (name "ADDR4") (class "Default")
      (node (ref "IC3") (pin "12") (pinfunction "5Q_12") (pintype "tri_state"))
      (node (ref "X2") (pin "A8") (pinfunction "B_A8") (pintype "passive"))
    )
    (net (code "40") (name "ADDR5") (class "Default")
      (node (ref "IC3") (pin "15") (pinfunction "6Q_15") (pintype "tri_state"))
      (node (ref "X2") (pin "A9") (pinfunction "B_A9") (pintype "passive"))
    )
    (net (code "41") (name "ADDR6") (class "Default")
      (node (ref "IC3") (pin "16") (pinfunction "7Q_16") (pintype "tri_state"))
      (node (ref "X2") (pin "A10") (pinfunction "B_A10") (pintype "passive"))
    )
    (net (code "42") (name "ADDR7") (class "Default")
      (node (ref "IC3") (pin "19") (pinfunction "8Q_19") (pintype "tri_state"))
      (node (ref "X2") (pin "A11") (pinfunction "B_A11") (pintype "passive"))
    )
    (net (code "43") (name "ADDR8") (class "Default")
      (node (ref "IC4") (pin "2") (pinfunction "1Q_2") (pintype "tri_state"))
      (node (ref "X2") (pin "A12") (pinfunction "B_A12") (pintype "passive"))
    )
    (net (code "44") (name "ADDR9") (class "Default")
      (node (ref "IC4") (pin "5") (pinfunction "2Q_5") (pintype "tri_state"))
      (node (ref "X2") (pin "A13") (pinfunction "B_A13") (pintype "passive"))
    )
    (net (code "45") (name "ADDR10") (class "Default")
      (node (ref "IC4") (pin "6") (pinfunction "3Q_6") (pintype "tri_state"))
      (node (ref "X2") (pin "A14") (pinfunction "B_A14") (pintype "passive"))
    )
    (net (code "46") (name "ADDR11") (class "Default")
      (node (ref "IC4") (pin "9") (pinfunction "4Q_9") (pintype "tri_state"))
      (node (ref "X2") (pin "A15") (pinfunction "B_A15") (pintype "passive"))
    )
    (net (code "47") (name "ADDR12") (class "Default")
      (node (ref "IC4") (pin "12") (pinfunction "5Q_12") (pintype "tri_state"))
      (node (ref "X2") (pin "A16") (pinfunction "B_A16") (pintype "passive"))
    )
    (net (code "48") (name "ADDR13") (class "Default")
      (node (ref "IC4") (pin "15") (pinfunction "6Q_15") (pintype "tri_state"))
      (node (ref "X2") (pin "A17") (pinfunction "B_A17") (pintype "passive"))
    )
    (net (code "49") (name "ADDR14") (class "Default")
      (node (ref "IC4") (pin "16") (pinfunction "7Q_16") (pintype "tri_state"))
      (node (ref "X2") (pin "A18") (pinfunction "B_A18") (pintype "passive"))
    )
    (net (code "50") (name "ADDR15") (class "Default")
      (node (ref "IC4") (pin "19") (pinfunction "8Q_19") (pintype "tri_state"))
      (node (ref "X2") (pin "A19") (pinfunction "B_A19") (pintype "passive"))
    )
    (net (code "51") (name "ALU-FUNC") (class "Default")
      (node (ref "X2") (pin "B27") (pinfunction "B_B27") (pintype "passive"))
    )
    (net (code "52") (name "ALU0") (class "Default")
      (node (ref "X2") (pin "B24") (pinfunction "B_B24") (pintype "passive"))
    )
    (net (code "53") (name "ALU1") (class "Default")
      (node (ref "X2") (pin "B25") (pinfunction "B_B25") (pintype "passive"))
    )
    (net (code "54") (name "ALU2") (class "Default")
      (node (ref "X2") (pin "B26") (pinfunction "B_B26") (pintype "passive"))
    )
    (net (code "55") (name "ALU3") (class "Default")
      (node (ref "X2") (pin "B3") (pinfunction "B_B3") (pintype "passive"))
    )
    (net (code "56") (name "BR-COND") (class "Default")
      (node (ref "X2") (pin "C8") (pinfunction "B_C8") (pintype "passive"))
    )
    (net (code "57") (name "BR-REG-LD-HI") (class "Default")
      (node (ref "X2") (pin "C6") (pinfunction "B_C6") (pintype "passive"))
    )
    (net (code "58") (name "BR-REG-LD-LO") (class "Default")
      (node (ref "X2") (pin "C3") (pinfunction "B_C3") (pintype "passive"))
    )
    (net (code "59") (name "BR-REG-OUT") (class "Default")
      (node (ref "X2") (pin "C7") (pinfunction "B_C7") (pintype "passive"))
    )
    (net (code "60") (name "BRD-ADDR-REG0") (class "Default")
      (node (ref "IC2") (pin "14") (pinfunction "A_14") (pintype "input"))
      (node (ref "IC2") (pin "2") (pinfunction "A_2") (pintype "input"))
      (node (ref "X2") (pin "B5") (pinfunction "B_B5") (pintype "passive"))
    )
    (net (code "61") (name "BRD-ADDR-REG1") (class "Default")
      (node (ref "IC2") (pin "13") (pinfunction "B_13") (pintype "input"))
      (node (ref "IC2") (pin "3") (pinfunction "B_3") (pintype "input"))
      (node (ref "X2") (pin "B6") (pinfunction "B_B6") (pintype "passive"))
    )
    (net (code "62") (name "BRD-IN-ID0") (class "Default")
      (node (ref "IC12") (pin "14") (pinfunction "A_14") (pintype "input"))
      (node (ref "X2") (pin "B18") (pinfunction "B_B18") (pintype "passive"))
    )
    (net (code "63") (name "BRD-IN-ID1") (class "Default")
      (node (ref "IC12") (pin "13") (pinfunction "B_13") (pintype "input"))
      (node (ref "X2") (pin "B19") (pinfunction "B_B19") (pintype "passive"))
    )
    (net (code "64") (name "BRD-OUT-ID0") (class "Default")
      (node (ref "IC11") (pin "14") (pinfunction "A_14") (pintype "input"))
      (node (ref "X2") (pin "B14") (pinfunction "B_B14") (pintype "passive"))
    )
    (net (code "65") (name "BRD-OUT-ID1") (class "Default")
      (node (ref "IC11") (pin "13") (pinfunction "B_13") (pintype "input"))
      (node (ref "X2") (pin "B15") (pinfunction "B_B15") (pintype "passive"))
    )
    (net (code "66") (name "BUS-DIR") (class "Default")
      (node (ref "IC6") (pin "8") (pinfunction "O_8") (pintype "output"))
      (node (ref "IC7") (pin "1") (pinfunction "DIR_1") (pintype "input"))
      (node (ref "IC8") (pin "1") (pinfunction "DIR_1") (pintype "input"))
      (node (ref "IC9") (pin "1") (pinfunction "DIR_1") (pintype "input"))
    )
    (net (code "67") (name "CLK0H") (class "Default")
      (node (ref "IC14") (pin "4") (pinfunction "O_4") (pintype "output"))
      (node (ref "IC16") (pin "11") (pinfunction "CLK_11") (pintype "input"))
      (node (ref "JP5") (pin "23") (pinfunction "23_23") (pintype "passive"))
    )
    (net (code "68") (name "CLK0L") (class "Default")
      (node (ref "IC14") (pin "1") (pinfunction "O_1") (pintype "output"))
      (node (ref "IC15") (pin "11") (pinfunction "CLK_11") (pintype "input"))
      (node (ref "JP5") (pin "25") (pinfunction "25_25") (pintype "passive"))
    )
    (net (code "69") (name "CLK1H") (class "Default")
      (node (ref "IC14") (pin "13") (pinfunction "O_13") (pintype "output"))
      (node (ref "IC18") (pin "11") (pinfunction "CLK_11") (pintype "input"))
      (node (ref "JP5") (pin "19") (pinfunction "19_19") (pintype "passive"))
    )
    (net (code "70") (name "CLK1L") (class "Default")
      (node (ref "IC14") (pin "10") (pinfunction "O_10") (pintype "output"))
      (node (ref "IC17") (pin "11") (pinfunction "CLK_11") (pintype "input"))
      (node (ref "JP5") (pin "21") (pinfunction "21_21") (pintype "passive"))
    )
    (net (code "71") (name "CLK2H") (class "Default")
      (node (ref "IC20") (pin "4") (pinfunction "O_4") (pintype "output"))
      (node (ref "IC22") (pin "11") (pinfunction "CLK_11") (pintype "input"))
      (node (ref "JP5") (pin "24") (pinfunction "24_24") (pintype "passive"))
    )
    (net (code "72") (name "CLK2L") (class "Default")
      (node (ref "IC20") (pin "1") (pinfunction "O_1") (pintype "output"))
      (node (ref "IC21") (pin "11") (pinfunction "CLK_11") (pintype "input"))
      (node (ref "JP5") (pin "26") (pinfunction "26_26") (pintype "passive"))
    )
    (net (code "73") (name "CLK3H") (class "Default")
      (node (ref "IC20") (pin "13") (pinfunction "O_13") (pintype "output"))
      (node (ref "IC24") (pin "11") (pinfunction "CLK_11") (pintype "input"))
      (node (ref "JP5") (pin "20") (pinfunction "20_20") (pintype "passive"))
    )
    (net (code "74") (name "CLK3L") (class "Default")
      (node (ref "IC20") (pin "10") (pinfunction "O_10") (pintype "output"))
      (node (ref "IC23") (pin "11") (pinfunction "CLK_11") (pintype "input"))
      (node (ref "JP5") (pin "22") (pinfunction "22_22") (pintype "passive"))
    )
    (net (code "75") (name "DATA-REG-IN-ID0") (class "Default")
      (node (ref "IC12") (pin "2") (pinfunction "A_2") (pintype "input"))
      (node (ref "X2") (pin "B16") (pinfunction "B_B16") (pintype "passive"))
    )
    (net (code "76") (name "DATA-REG-IN-ID1") (class "Default")
      (node (ref "IC12") (pin "3") (pinfunction "B_3") (pintype "input"))
      (node (ref "X2") (pin "B17") (pinfunction "B_B17") (pintype "passive"))
    )
    (net (code "77") (name "DATA-REG-OUT-ID0") (class "Default")
      (node (ref "IC11") (pin "2") (pinfunction "A_2") (pintype "input"))
      (node (ref "X2") (pin "B12") (pinfunction "B_B12") (pintype "passive"))
    )
    (net (code "78") (name "DATA-REG-OUT-ID1") (class "Default")
      (node (ref "IC11") (pin "3") (pinfunction "B_3") (pintype "input"))
      (node (ref "X2") (pin "B13") (pinfunction "B_B13") (pintype "passive"))
    )
    (net (code "79") (name "DATA-REG-RD-HI") (class "Default")
      (node (ref "IC1") (pin "5") (pinfunction "I_5") (pintype "input"))
      (node (ref "X2") (pin "B22") (pinfunction "B_B22") (pintype "passive"))
    )
    (net (code "80") (name "DATA-REG-RD-LO") (class "Default")
      (node (ref "IC1") (pin "1") (pinfunction "I_1") (pintype "input"))
      (node (ref "X2") (pin "B20") (pinfunction "B_B20") (pintype "passive"))
    )
    (net (code "81") (name "DATA-REG-WR-HI") (class "Default")
      (node (ref "IC1") (pin "9") (pinfunction "I_9") (pintype "input"))
      (node (ref "X2") (pin "B23") (pinfunction "B_B23") (pintype "passive"))
    )
    (net (code "82") (name "DATA-REG-WR-LO") (class "Default")
      (node (ref "IC1") (pin "3") (pinfunction "I_3") (pintype "input"))
      (node (ref "X2") (pin "B21") (pinfunction "B_B21") (pintype "passive"))
    )
    (net (code "83") (name "DATA0") (class "Default")
      (node (ref "IC7") (pin "2") (pinfunction "A1_2") (pintype "bidirectional"))
      (node (ref "IC9") (pin "2") (pinfunction "A1_2") (pintype "bidirectional"))
      (node (ref "X2") (pin "A20") (pinfunction "B_A20") (pintype "passive"))
    )
    (net (code "84") (name "DATA1") (class "Default")
      (node (ref "IC7") (pin "3") (pinfunction "A2_3") (pintype "bidirectional"))
      (node (ref "IC9") (pin "3") (pinfunction "A2_3") (pintype "bidirectional"))
      (node (ref "X2") (pin "A21") (pinfunction "B_A21") (pintype "passive"))
    )
    (net (code "85") (name "DATA2") (class "Default")
      (node (ref "IC7") (pin "4") (pinfunction "A3_4") (pintype "bidirectional"))
      (node (ref "IC9") (pin "4") (pinfunction "A3_4") (pintype "bidirectional"))
      (node (ref "X2") (pin "A22") (pinfunction "B_A22") (pintype "passive"))
    )
    (net (code "86") (name "DATA3") (class "Default")
      (node (ref "IC7") (pin "5") (pinfunction "A4_5") (pintype "bidirectional"))
      (node (ref "IC9") (pin "5") (pinfunction "A4_5") (pintype "bidirectional"))
      (node (ref "X2") (pin "A23") (pinfunction "B_A23") (pintype "passive"))
    )
    (net (code "87") (name "DATA4") (class "Default")
      (node (ref "IC7") (pin "6") (pinfunction "A5_6") (pintype "bidirectional"))
      (node (ref "IC9") (pin "6") (pinfunction "A5_6") (pintype "bidirectional"))
      (node (ref "X2") (pin "A24") (pinfunction "B_A24") (pintype "passive"))
    )
    (net (code "88") (name "DATA5") (class "Default")
      (node (ref "IC7") (pin "7") (pinfunction "A6_7") (pintype "bidirectional"))
      (node (ref "IC9") (pin "7") (pinfunction "A6_7") (pintype "bidirectional"))
      (node (ref "X2") (pin "A25") (pinfunction "B_A25") (pintype "passive"))
    )
    (net (code "89") (name "DATA6") (class "Default")
      (node (ref "IC7") (pin "8") (pinfunction "A7_8") (pintype "bidirectional"))
      (node (ref "IC9") (pin "8") (pinfunction "A7_8") (pintype "bidirectional"))
      (node (ref "X2") (pin "A26") (pinfunction "B_A26") (pintype "passive"))
    )
    (net (code "90") (name "DATA7") (class "Default")
      (node (ref "IC7") (pin "9") (pinfunction "A8_9") (pintype "bidirectional"))
      (node (ref "IC9") (pin "9") (pinfunction "A8_9") (pintype "bidirectional"))
      (node (ref "X2") (pin "A27") (pinfunction "B_A27") (pintype "passive"))
    )
    (net (code "91") (name "DATA8") (class "Default")
      (node (ref "IC8") (pin "2") (pinfunction "A1_2") (pintype "bidirectional"))
      (node (ref "X2") (pin "C23") (pinfunction "B_C23") (pintype "passive"))
    )
    (net (code "92") (name "DATA9") (class "Default")
      (node (ref "IC8") (pin "3") (pinfunction "A2_3") (pintype "bidirectional"))
      (node (ref "X2") (pin "C24") (pinfunction "B_C24") (pintype "passive"))
    )
    (net (code "93") (name "DATA10") (class "Default")
      (node (ref "IC8") (pin "4") (pinfunction "A3_4") (pintype "bidirectional"))
      (node (ref "X2") (pin "C25") (pinfunction "B_C25") (pintype "passive"))
    )
    (net (code "94") (name "DATA11") (class "Default")
      (node (ref "IC8") (pin "5") (pinfunction "A4_5") (pintype "bidirectional"))
      (node (ref "X2") (pin "C26") (pinfunction "B_C26") (pintype "passive"))
    )
    (net (code "95") (name "DATA12") (class "Default")
      (node (ref "IC8") (pin "6") (pinfunction "A5_6") (pintype "bidirectional"))
      (node (ref "X2") (pin "C27") (pinfunction "B_C27") (pintype "passive"))
    )
    (net (code "96") (name "DATA13") (class "Default")
      (node (ref "IC8") (pin "7") (pinfunction "A6_7") (pintype "bidirectional"))
      (node (ref "X2") (pin "C28") (pinfunction "B_C28") (pintype "passive"))
    )
    (net (code "97") (name "DATA14") (class "Default")
      (node (ref "IC8") (pin "8") (pinfunction "A7_8") (pintype "bidirectional"))
      (node (ref "X2") (pin "C29") (pinfunction "B_C29") (pintype "passive"))
    )
    (net (code "98") (name "DATA15") (class "Default")
      (node (ref "IC8") (pin "9") (pinfunction "A8_9") (pintype "bidirectional"))
      (node (ref "X2") (pin "C30") (pinfunction "B_C30") (pintype "passive"))
    )
    (net (code "99") (name "DIR") (class "Default")
      (node (ref "X2") (pin "A29") (pinfunction "B_A29") (pintype "passive"))
    )
    (net (code "100") (name "GND") (class "Default")
      (node (ref "C1") (pin "2") (pinfunction "2_2") (pintype "passive"))
      (node (ref "C10") (pin "2") (pinfunction "2_2") (pintype "passive"))
      (node (ref "C12") (pin "2") (pinfunction "2_2") (pintype "passive"))
      (node (ref "C13") (pin "2") (pinfunction "2_2") (pintype "passive"))
      (node (ref "C14") (pin "2") (pinfunction "2_2") (pintype "passive"))
      (node (ref "C15") (pin "2") (pinfunction "2_2") (pintype "passive"))
      (node (ref "C16") (pin "2") (pinfunction "2_2") (pintype "passive"))
      (node (ref "C17") (pin "2") (pinfunction "2_2") (pintype "passive"))
      (node (ref "C18") (pin "2") (pinfunction "2_2") (pintype "passive"))
      (node (ref "C19") (pin "2") (pinfunction "2_2") (pintype "passive"))
      (node (ref "C2") (pin "2") (pinfunction "2_2") (pintype "passive"))
      (node (ref "C20") (pin "2") (pinfunction "2_2") (pintype "passive"))
      (node (ref "C21") (pin "2") (pinfunction "2_2") (pintype "passive"))
      (node (ref "C22") (pin "2") (pinfunction "2_2") (pintype "passive"))
      (node (ref "C23") (pin "2") (pinfunction "2_2") (pintype "passive"))
      (node (ref "C24") (pin "2") (pinfunction "2_2") (pintype "passive"))
      (node (ref "C3") (pin "2") (pinfunction "2_2") (pintype "passive"))
      (node (ref "C4") (pin "2") (pinfunction "2_2") (pintype "passive"))
      (node (ref "C5") (pin "2") (pinfunction "2_2") (pintype "passive"))
      (node (ref "C6") (pin "2") (pinfunction "2_2") (pintype "passive"))
      (node (ref "C7") (pin "2") (pinfunction "2_2") (pintype "passive"))
      (node (ref "C8") (pin "2") (pinfunction "2_2") (pintype "passive"))
      (node (ref "C9") (pin "2") (pinfunction "2_2") (pintype "passive"))
      (node (ref "JP5") (pin "1") (pinfunction "1_1") (pintype "passive"))
      (node (ref "JP5") (pin "2") (pinfunction "2_2") (pintype "passive"))
      (node (ref "JP5") (pin "27") (pinfunction "27_27") (pintype "passive"))
      (node (ref "JP5") (pin "28") (pinfunction "28_28") (pintype "passive"))
      (node (ref "PWR1") (pin "K") (pinfunction "C_K") (pintype "passive"))
      (node (ref "X2") (pin "A1") (pinfunction "B_A1") (pintype "passive"))
      (node (ref "X2") (pin "A32") (pinfunction "B_A32") (pintype "passive"))
      (node (ref "X2") (pin "B1") (pinfunction "B_B1") (pintype "passive"))
      (node (ref "X2") (pin "B32") (pinfunction "B_B32") (pintype "passive"))
      (node (ref "X2") (pin "C1") (pinfunction "B_C1") (pintype "passive"))
      (node (ref "X2") (pin "C32") (pinfunction "B_C32") (pintype "passive"))
    )
    (net (code "101") (name "H{slash}L-SWAP") (class "Default")
      (node (ref "IC5") (pin "13") (pinfunction "I1_13") (pintype "input"))
      (node (ref "IC6") (pin "1") (pinfunction "I0_1") (pintype "input"))
      (node (ref "IC6") (pin "2") (pinfunction "I1_2") (pintype "input"))
      (node (ref "X2") (pin "A30") (pinfunction "B_A30") (pintype "passive"))
    )
    (net (code "102") (name "INT") (class "Default")
      (node (ref "X2") (pin "C14") (pinfunction "B_C14") (pintype "passive"))
    )
    (net (code "103") (name "INT-ACK") (class "Default")
      (node (ref "X2") (pin "A3") (pinfunction "B_A3") (pintype "passive"))
    )
    (net (code "104") (name "IO-ADDR") (class "Default")
      (node (ref "X2") (pin "C13") (pinfunction "B_C13") (pintype "passive"))
    )
    (net (code "105") (name "I{slash}D-REG-DN") (class "Default")
      (node (ref "X2") (pin "B9") (pinfunction "B_B9") (pintype "passive"))
    )
    (net (code "106") (name "I{slash}D-REG-LD") (class "Default")
      (node (ref "X2") (pin "C4") (pinfunction "B_C4") (pintype "passive"))
    )
    (net (code "107") (name "I{slash}D-REG-OUT") (class "Default")
      (node (ref "X2") (pin "C5") (pinfunction "B_C5") (pintype "passive"))
    )
    (net (code "108") (name "I{slash}D-REG-UP") (class "Default")
      (node (ref "X2") (pin "B10") (pinfunction "B_B10") (pintype "passive"))
    )
    (net (code "109") (name "I{slash}O-RD") (class "Default")
      (node (ref "X2") (pin "C12") (pinfunction "B_C12") (pintype "passive"))
    )
    (net (code "110") (name "I{slash}O-WR") (class "Default")
      (node (ref "X2") (pin "C11") (pinfunction "B_C11") (pintype "passive"))
    )
    (net (code "111") (name "LD-AC") (class "Default")
      (node (ref "X2") (pin "B28") (pinfunction "B_B28") (pintype "passive"))
    )
    (net (code "112") (name "MEM-RD") (class "Default")
      (node (ref "X2") (pin "C10") (pinfunction "B_C10") (pintype "passive"))
    )
    (net (code "113") (name "MEM-WR") (class "Default")
      (node (ref "X2") (pin "C9") (pinfunction "B_C9") (pintype "passive"))
    )
    (net (code "114") (name "Net-(IC1E-O)") (class "Default")
      (node (ref "IC1") (pin "10") (pinfunction "O_10") (pintype "output"))
      (node (ref "IC2") (pin "1") (pinfunction "G_1") (pintype "input"))
    )
    (net (code "115") (name "Net-(IC1F-I)") (class "Default")
      (node (ref "IC1") (pin "13") (pinfunction "I_13") (pintype "input"))
      (node (ref "JP1") (pin "2") (pinfunction "2_2") (pintype "passive"))
      (node (ref "JP1") (pin "4") (pinfunction "4_4") (pintype "passive"))
      (node (ref "JP1") (pin "6") (pinfunction "6_6") (pintype "passive"))
      (node (ref "JP1") (pin "8") (pinfunction "8_8") (pintype "passive"))
    )
    (net (code "116") (name "Net-(IC1F-O)") (class "Default")
      (node (ref "IC1") (pin "12") (pinfunction "O_12") (pintype "output"))
      (node (ref "IC3") (pin "11") (pinfunction "CLK_11") (pintype "input"))
      (node (ref "IC4") (pin "11") (pinfunction "CLK_11") (pintype "input"))
    )
    (net (code "117") (name "Net-(IC2A-Y0)") (class "Default")
      (node (ref "IC2") (pin "4") (pinfunction "Y0_4") (pintype "output"))
      (node (ref "JP1") (pin "1") (pinfunction "1_1") (pintype "passive"))
    )
    (net (code "118") (name "Net-(IC2A-Y1)") (class "Default")
      (node (ref "IC2") (pin "5") (pinfunction "Y1_5") (pintype "output"))
      (node (ref "JP1") (pin "3") (pinfunction "3_3") (pintype "passive"))
    )
    (net (code "119") (name "Net-(IC2A-Y2)") (class "Default")
      (node (ref "IC2") (pin "6") (pinfunction "Y2_6") (pintype "output"))
      (node (ref "JP1") (pin "5") (pinfunction "5_5") (pintype "passive"))
    )
    (net (code "120") (name "Net-(IC2A-Y3)") (class "Default")
      (node (ref "IC2") (pin "7") (pinfunction "Y3_7") (pintype "output"))
      (node (ref "JP1") (pin "7") (pinfunction "7_7") (pintype "passive"))
    )
    (net (code "121") (name "Net-(IC2B-G)") (class "Default")
      (node (ref "IC2") (pin "15") (pinfunction "G_15") (pintype "input"))
      (node (ref "IC6") (pin "6") (pinfunction "O_6") (pintype "output"))
    )
    (net (code "122") (name "Net-(IC2B-Y0)") (class "Default")
      (node (ref "IC2") (pin "12") (pinfunction "Y0_12") (pintype "output"))
      (node (ref "JP2") (pin "1") (pinfunction "1_1") (pintype "passive"))
    )
    (net (code "123") (name "Net-(IC2B-Y1)") (class "Default")
      (node (ref "IC2") (pin "11") (pinfunction "Y1_11") (pintype "output"))
      (node (ref "JP2") (pin "3") (pinfunction "3_3") (pintype "passive"))
    )
    (net (code "124") (name "Net-(IC2B-Y2)") (class "Default")
      (node (ref "IC2") (pin "10") (pinfunction "Y2_10") (pintype "output"))
      (node (ref "JP2") (pin "5") (pinfunction "5_5") (pintype "passive"))
    )
    (net (code "125") (name "Net-(IC2B-Y3)") (class "Default")
      (node (ref "IC2") (pin "9") (pinfunction "Y3_9") (pintype "output"))
      (node (ref "JP2") (pin "7") (pinfunction "7_7") (pintype "passive"))
    )
    (net (code "126") (name "Net-(IC3A-OC)") (class "Default")
      (node (ref "IC3") (pin "1") (pinfunction "OC_1") (pintype "input"))
      (node (ref "IC4") (pin "1") (pinfunction "OC_1") (pintype "input"))
      (node (ref "JP2") (pin "2") (pinfunction "2_2") (pintype "passive"))
      (node (ref "JP2") (pin "4") (pinfunction "4_4") (pintype "passive"))
      (node (ref "JP2") (pin "6") (pinfunction "6_6") (pintype "passive"))
      (node (ref "JP2") (pin "8") (pinfunction "8_8") (pintype "passive"))
    )
    (net (code "127") (name "Net-(IC5A-O)") (class "Default")
      (node (ref "IC5") (pin "10") (pinfunction "I1_10") (pintype "input"))
      (node (ref "IC5") (pin "12") (pinfunction "I0_12") (pintype "input"))
      (node (ref "IC5") (pin "3") (pinfunction "O_3") (pintype "output"))
      (node (ref "IC5") (pin "4") (pinfunction "I0_4") (pintype "input"))
      (node (ref "IC5") (pin "5") (pinfunction "I1_5") (pintype "input"))
    )
    (net (code "128") (name "Net-(IC5B-O)") (class "Default")
      (node (ref "IC5") (pin "6") (pinfunction "O_6") (pintype "output"))
      (node (ref "IC8") (pin "19") (pinfunction "G_19") (pintype "input"))
    )
    (net (code "129") (name "Net-(IC5C-I0)") (class "Default")
      (node (ref "IC5") (pin "9") (pinfunction "I0_9") (pintype "input"))
      (node (ref "IC6") (pin "3") (pinfunction "O_3") (pintype "output"))
    )
    (net (code "130") (name "Net-(IC5C-O)") (class "Default")
      (node (ref "IC5") (pin "8") (pinfunction "O_8") (pintype "output"))
      (node (ref "IC7") (pin "19") (pinfunction "G_19") (pintype "input"))
    )
    (net (code "131") (name "Net-(IC5D-O)") (class "Default")
      (node (ref "IC5") (pin "11") (pinfunction "O_11") (pintype "output"))
      (node (ref "IC9") (pin "19") (pinfunction "G_19") (pintype "input"))
    )
    (net (code "132") (name "Net-(IC11B-Y0)") (class "Default")
      (node (ref "IC11") (pin "12") (pinfunction "Y0_12") (pintype "output"))
      (node (ref "JP3") (pin "1") (pinfunction "1_1") (pintype "passive"))
    )
    (net (code "133") (name "Net-(IC11B-Y1)") (class "Default")
      (node (ref "IC11") (pin "11") (pinfunction "Y1_11") (pintype "output"))
      (node (ref "JP3") (pin "3") (pinfunction "3_3") (pintype "passive"))
    )
    (net (code "134") (name "Net-(IC11B-Y2)") (class "Default")
      (node (ref "IC11") (pin "10") (pinfunction "Y2_10") (pintype "output"))
      (node (ref "JP3") (pin "5") (pinfunction "5_5") (pintype "passive"))
    )
    (net (code "135") (name "Net-(IC11B-Y3)") (class "Default")
      (node (ref "IC11") (pin "9") (pinfunction "Y3_9") (pintype "output"))
      (node (ref "JP3") (pin "7") (pinfunction "7_7") (pintype "passive"))
    )
    (net (code "136") (name "Net-(IC12B-Y0)") (class "Default")
      (node (ref "IC12") (pin "12") (pinfunction "Y0_12") (pintype "output"))
      (node (ref "JP4") (pin "1") (pinfunction "1_1") (pintype "passive"))
    )
    (net (code "137") (name "Net-(IC12B-Y1)") (class "Default")
      (node (ref "IC12") (pin "11") (pinfunction "Y1_11") (pintype "output"))
      (node (ref "JP4") (pin "3") (pinfunction "3_3") (pintype "passive"))
    )
    (net (code "138") (name "Net-(IC12B-Y2)") (class "Default")
      (node (ref "IC12") (pin "10") (pinfunction "Y2_10") (pintype "output"))
      (node (ref "JP4") (pin "5") (pinfunction "5_5") (pintype "passive"))
    )
    (net (code "139") (name "Net-(IC12B-Y3)") (class "Default")
      (node (ref "IC12") (pin "9") (pinfunction "Y3_9") (pintype "output"))
      (node (ref "JP4") (pin "7") (pinfunction "7_7") (pintype "passive"))
    )
    (net (code "140") (name "Net-(IC13A-O)") (class "Default")
      (node (ref "IC13") (pin "3") (pinfunction "O_3") (pintype "output"))
      (node (ref "IC15") (pin "1") (pinfunction "OC_1") (pintype "input"))
    )
    (net (code "141") (name "Net-(IC13B-O)") (class "Default")
      (node (ref "IC13") (pin "6") (pinfunction "O_6") (pintype "output"))
      (node (ref "IC16") (pin "1") (pinfunction "OC_1") (pintype "input"))
    )
    (net (code "142") (name "Net-(IC13C-O)") (class "Default")
      (node (ref "IC13") (pin "8") (pinfunction "O_8") (pintype "output"))
      (node (ref "IC17") (pin "1") (pinfunction "OC_1") (pintype "input"))
    )
    (net (code "143") (name "Net-(IC13D-O)") (class "Default")
      (node (ref "IC13") (pin "11") (pinfunction "O_11") (pintype "output"))
      (node (ref "IC18") (pin "1") (pinfunction "OC_1") (pintype "input"))
    )
    (net (code "144") (name "Net-(IC19A-O)") (class "Default")
      (node (ref "IC19") (pin "3") (pinfunction "O_3") (pintype "output"))
      (node (ref "IC21") (pin "1") (pinfunction "OC_1") (pintype "input"))
    )
    (net (code "145") (name "Net-(IC19B-O)") (class "Default")
      (node (ref "IC19") (pin "6") (pinfunction "O_6") (pintype "output"))
      (node (ref "IC22") (pin "1") (pinfunction "OC_1") (pintype "input"))
    )
    (net (code "146") (name "Net-(IC19C-O)") (class "Default")
      (node (ref "IC19") (pin "8") (pinfunction "O_8") (pintype "output"))
      (node (ref "IC23") (pin "1") (pinfunction "OC_1") (pintype "input"))
    )
    (net (code "147") (name "Net-(IC19D-O)") (class "Default")
      (node (ref "IC19") (pin "11") (pinfunction "O_11") (pintype "output"))
      (node (ref "IC24") (pin "1") (pinfunction "OC_1") (pintype "input"))
    )
    (net (code "148") (name "Net-(PWR1-PadA)") (class "Default")
      (node (ref "PWR1") (pin "A") (pinfunction "A_A") (pintype "passive"))
      (node (ref "R2") (pin "1") (pinfunction "1_1") (pintype "passive"))
    )
    (net (code "149") (name "RD-AC") (class "Default")
      (node (ref "X2") (pin "B29") (pinfunction "B_B29") (pintype "passive"))
    )
    (net (code "150") (name "REG-FUNC") (class "Default")
      (node (ref "IC6") (pin "12") (pinfunction "I0_12") (pintype "input"))
      (node (ref "IC6") (pin "13") (pinfunction "I1_13") (pintype "input"))
      (node (ref "X2") (pin "B7") (pinfunction "B_B7") (pintype "passive"))
    )
    (net (code "151") (name "RESET") (class "Default")
      (node (ref "X2") (pin "B11") (pinfunction "B_B11") (pintype "passive"))
    )
    (net (code "152") (name "SP{slash}PC-ADDR-OUT") (class "Default")
      (node (ref "X2") (pin "C18") (pinfunction "B_C18") (pintype "passive"))
    )
    (net (code "153") (name "SP{slash}PC-DATA-OUT-HI") (class "Default")
      (node (ref "X2") (pin "C17") (pinfunction "B_C17") (pintype "passive"))
    )
    (net (code "154") (name "SP{slash}PC-DATA-OUT-LO") (class "Default")
      (node (ref "X2") (pin "C16") (pinfunction "B_C16") (pintype "passive"))
    )
    (net (code "155") (name "SP{slash}PC-DN") (class "Default")
      (node (ref "X2") (pin "C21") (pinfunction "B_C21") (pintype "passive"))
    )
    (net (code "156") (name "SP{slash}PC-LD-HI") (class "Default")
      (node (ref "X2") (pin "C20") (pinfunction "B_C20") (pintype "passive"))
    )
    (net (code "157") (name "SP{slash}PC-LD-LO") (class "Default")
      (node (ref "X2") (pin "C19") (pinfunction "B_C19") (pintype "passive"))
    )
    (net (code "158") (name "SP{slash}PC-SEL") (class "Default")
      (node (ref "X2") (pin "C15") (pinfunction "B_C15") (pintype "passive"))
    )
    (net (code "159") (name "SP{slash}PC-UP") (class "Default")
      (node (ref "X2") (pin "C22") (pinfunction "B_C22") (pintype "passive"))
    )
    (net (code "160") (name "SR-LD") (class "Default")
      (node (ref "X2") (pin "A28") (pinfunction "B_A28") (pintype "passive"))
    )
    (net (code "161") (name "VCC") (class "Default")
      (node (ref "C1") (pin "1") (pinfunction "1_1") (pintype "passive"))
      (node (ref "C10") (pin "1") (pinfunction "1_1") (pintype "passive"))
      (node (ref "C12") (pin "1") (pinfunction "1_1") (pintype "passive"))
      (node (ref "C13") (pin "1") (pinfunction "1_1") (pintype "passive"))
      (node (ref "C14") (pin "1") (pinfunction "1_1") (pintype "passive"))
      (node (ref "C15") (pin "1") (pinfunction "1_1") (pintype "passive"))
      (node (ref "C16") (pin "1") (pinfunction "1_1") (pintype "passive"))
      (node (ref "C17") (pin "1") (pinfunction "1_1") (pintype "passive"))
      (node (ref "C18") (pin "1") (pinfunction "1_1") (pintype "passive"))
      (node (ref "C19") (pin "1") (pinfunction "1_1") (pintype "passive"))
      (node (ref "C2") (pin "1") (pinfunction "1_1") (pintype "passive"))
      (node (ref "C20") (pin "1") (pinfunction "1_1") (pintype "passive"))
      (node (ref "C21") (pin "1") (pinfunction "1_1") (pintype "passive"))
      (node (ref "C22") (pin "1") (pinfunction "1_1") (pintype "passive"))
      (node (ref "C23") (pin "1") (pinfunction "1_1") (pintype "passive"))
      (node (ref "C24") (pin "1") (pinfunction "1_1") (pintype "passive"))
      (node (ref "C3") (pin "1") (pinfunction "1_1") (pintype "passive"))
      (node (ref "C4") (pin "1") (pinfunction "1_1") (pintype "passive"))
      (node (ref "C5") (pin "1") (pinfunction "1_1") (pintype "passive"))
      (node (ref "C6") (pin "1") (pinfunction "1_1") (pintype "passive"))
      (node (ref "C7") (pin "1") (pinfunction "1_1") (pintype "passive"))
      (node (ref "C8") (pin "1") (pinfunction "1_1") (pintype "passive"))
      (node (ref "C9") (pin "1") (pinfunction "1_1") (pintype "passive"))
      (node (ref "R2") (pin "2") (pinfunction "2_2") (pintype "passive"))
      (node (ref "RN1") (pin "1") (pinfunction "1_1") (pintype "passive"))
      (node (ref "RN2") (pin "1") (pinfunction "1_1") (pintype "passive"))
      (node (ref "X2") (pin "A2") (pinfunction "B_A2") (pintype "passive"))
      (node (ref "X2") (pin "A31") (pinfunction "B_A31") (pintype "passive"))
      (node (ref "X2") (pin "B2") (pinfunction "B_B2") (pintype "passive"))
      (node (ref "X2") (pin "B31") (pinfunction "B_B31") (pintype "passive"))
      (node (ref "X2") (pin "C2") (pinfunction "B_C2") (pintype "passive"))
      (node (ref "X2") (pin "C31") (pinfunction "B_C31") (pintype "passive"))
    )
  )
)
